# Power_Management.net
KiCad netlist of a schematic drawn in Altium Designer
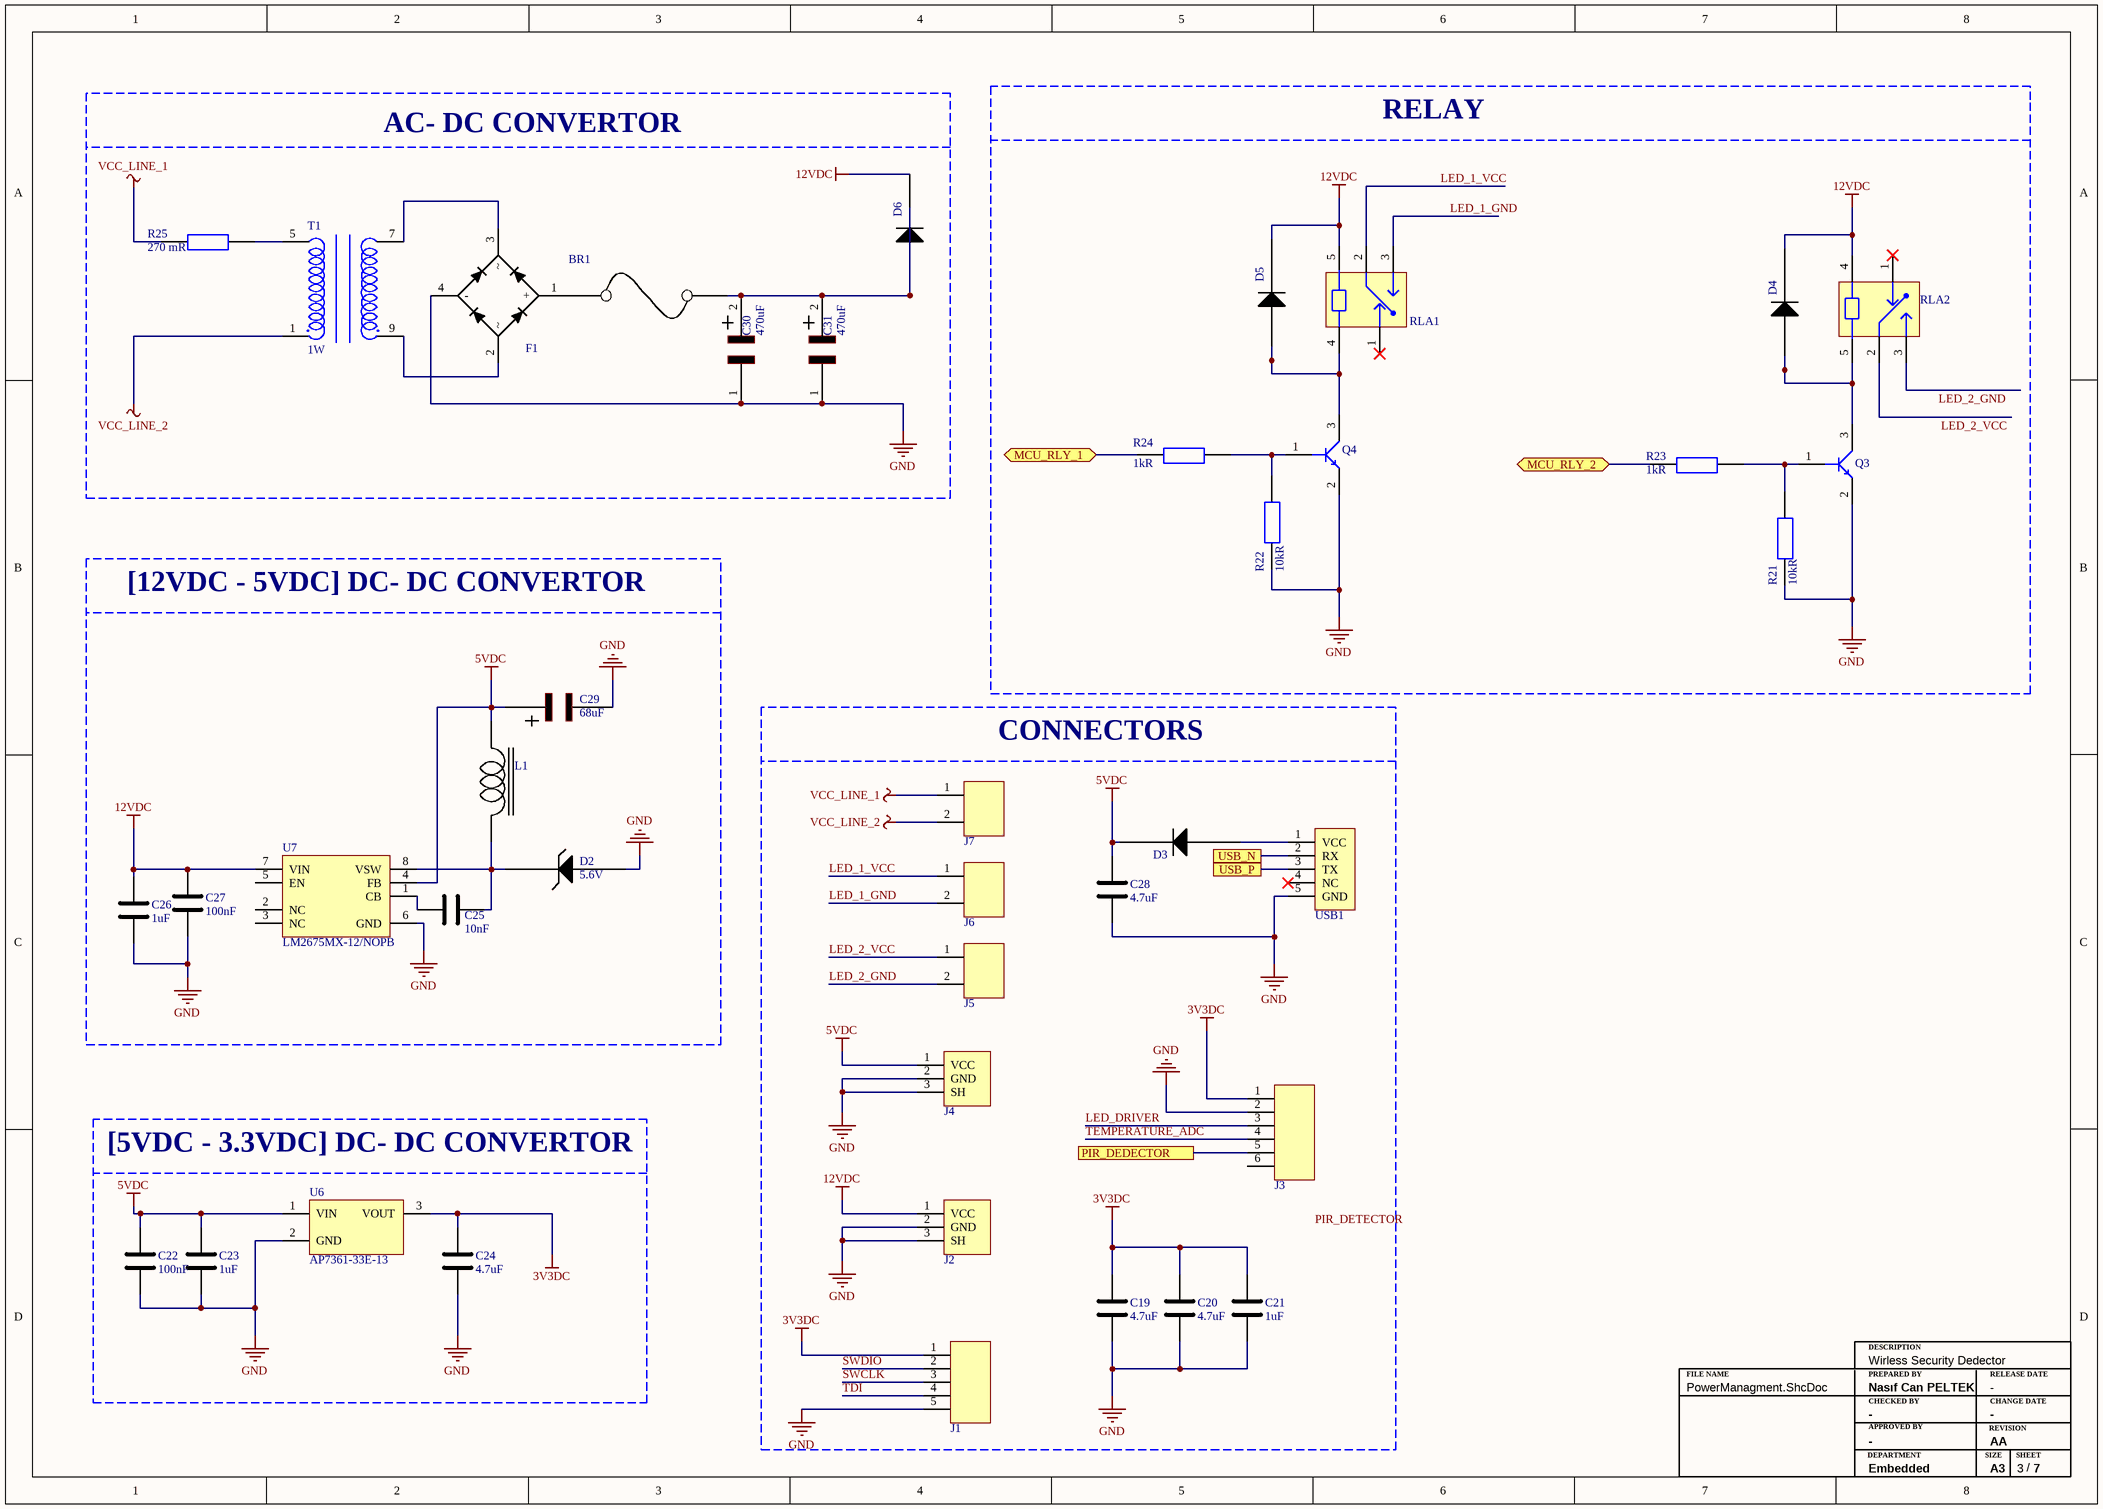
[diagram p0: Power_Management.SchDoc]

(export (version "E")
  (design (tool "Eeschema 10.0.6"))
  (components
    (comp (ref "BR1")
      (value "DB105S")
      (footprint "DB105S")
      (description "Bridge Rect 1PHASE 600V 1A Db-s")
      (fields
        (field (name "MANUFACTURER") "Sangdest Microelectronics")
        (field (name "DESIGNED BY") "Nasıf Can Peltek")
      )
      (libsource (lib "OV_00_Library") (part "DB105S"))
    )
    (comp (ref "C19")
      (value "CL21A475KAQNNNE")
      (footprint "CAP_805")
      (description "CAP CER 4.7UF 25V 10% 0805")
      (fields
        (field (name "MANUFACTURER") "Samsung")
        (field (name "TOLERANCE") "10%")
        (field (name "CAPACITANCE") "4.7uF")
        (field (name "DESIGNED BY") "Nasıf Can Peltek")
      )
      (libsource (lib "OV_00_Library") (part "CAP CER 4.7uF 0805"))
    )
    (comp (ref "C20")
      (value "CL21A475KAQNNNE")
      (footprint "CAP_805")
      (description "CAP CER 4.7UF 25V 10% 0805")
      (fields
        (field (name "MANUFACTURER") "Samsung")
        (field (name "TOLERANCE") "10%")
        (field (name "CAPACITANCE") "4.7uF")
        (field (name "DESIGNED BY") "Nasıf Can Peltek")
      )
      (libsource (lib "OV_00_Library") (part "CAP CER 4.7uF 0805"))
    )
    (comp (ref "C21")
      (value "CL21B105KBFNNNE")
      (footprint "CAP_805")
      (description "CAP CER 1UF 50V 10% 0805")
      (fields
        (field (name "MANUFACTURER") "Samsung")
        (field (name "TOLERANCE") "10%")
        (field (name "CAPACITANCE") "1uF")
        (field (name "DESIGNED BY") "Nasıf Can Peltek")
      )
      (libsource (lib "OV_00_Library") (part "CAP CER 1uF 0805"))
    )
    (comp (ref "C22")
      (value "C0603C104K5RAC7867")
      (footprint "CAP_603")
      (description "CAP CER 100nF 50V 10% SMD 0603")
      (fields
        (field (name "MANUFACTURER") "KEMET")
        (field (name "MANUFACTURER PART NUMBER") "C0603C104K5RACTU")
        (field (name "CAPACITANCE") "100nF")
        (field (name "DESIGNED BY") "Nasıf Can Peltek")
      )
      (libsource (lib "OV_00_Library") (part "CAP CER 100nF 0603"))
    )
    (comp (ref "C23")
      (value "CL21B105KBFNNNE")
      (footprint "CAP_805")
      (description "CAP CER 1UF 50V 10% 0805")
      (fields
        (field (name "MANUFACTURER") "Samsung")
        (field (name "TOLERANCE") "10%")
        (field (name "CAPACITANCE") "1uF")
        (field (name "DESIGNED BY") "Nasıf Can Peltek")
      )
      (libsource (lib "OV_00_Library") (part "CAP CER 1uF 0805"))
    )
    (comp (ref "C24")
      (value "CL21A475KAQNNNE")
      (footprint "CAP_805")
      (description "CAP CER 4.7UF 25V 10% 0805")
      (fields
        (field (name "MANUFACTURER") "Samsung")
        (field (name "TOLERANCE") "10%")
        (field (name "CAPACITANCE") "4.7uF")
        (field (name "DESIGNED BY") "Nasıf Can Peltek")
      )
      (libsource (lib "OV_00_Library") (part "CAP CER 4.7uF 0805"))
    )
    (comp (ref "C25")
      (value "0603B103K160CT")
      (footprint "CAP_603")
      (description "CAP CER 10nF 16V 10% SMD 0603")
      (fields
        (field (name "MANUFACTURER") "Walsin Technologies")
        (field (name "TOLERANCE") "10%")
        (field (name "CAPACITANCE") "10nF")
        (field (name "DESIGNED BY") "Nasıf Can Peltek")
      )
      (libsource (lib "OV_00_Library") (part "CAP CER 10nF 0603"))
    )
    (comp (ref "C26")
      (value "CL21B105KBFNNNE")
      (footprint "CAP_805")
      (description "CAP CER 1UF 50V 10% 0805")
      (fields
        (field (name "MANUFACTURER") "Samsung")
        (field (name "TOLERANCE") "10%")
        (field (name "CAPACITANCE") "1uF")
        (field (name "DESIGNED BY") "Nasıf Can Peltek")
      )
      (libsource (lib "OV_00_Library") (part "CAP CER 1uF 0805"))
    )
    (comp (ref "C27")
      (value "C0603C104K5RAC7867")
      (footprint "CAP_603")
      (description "CAP CER 100nF 50V 10% SMD 0603")
      (fields
        (field (name "MANUFACTURER") "KEMET")
        (field (name "MANUFACTURER PART NUMBER") "C0603C104K5RACTU")
        (field (name "CAPACITANCE") "100nF")
        (field (name "DESIGNED BY") "Nasıf Can Peltek")
      )
      (libsource (lib "OV_00_Library") (part "CAP CER 100nF 0603"))
    )
    (comp (ref "C28")
      (value "CL21A475KAQNNNE")
      (footprint "CAP_805")
      (description "CAP CER 4.7UF 25V 10% 0805")
      (fields
        (field (name "MANUFACTURER") "Samsung")
        (field (name "TOLERANCE") "10%")
        (field (name "CAPACITANCE") "4.7uF")
        (field (name "DESIGNED BY") "Nasıf Can Peltek")
      )
      (libsource (lib "OV_00_Library") (part "CAP CER 4.7uF 0805"))
    )
    (comp (ref "C29")
      (value "EEV686M035A9HAA")
      (footprint "CAP_EEV_Series")
      (description "Cap Aluminum Lytic 68uF 35V 20% (6.3 X 7.7mm)")
      (fields
        (field (name "MANUFACTURER") "KEMET")
        (field (name "TOLERANCE") "20%")
        (field (name "CAPACITANCE") "68uF")
        (field (name "DESIGNED BY") "Nasıf Can Peltek")
      )
      (libsource (lib "OV_00_Library") (part "CAP ALU 68uF"))
    )
    (comp (ref "C30")
      (value "ESH477M050AH4AA")
      (footprint "CAP_RADIAL_D10_P5")
      (description "Aluminum Electrolytic Capacitors Radial, Can  470 µF 50 V 2000 Hrs @ 105°C")
      (fields
        (field (name "MANUFACTURER") "KEMET")
        (field (name "TOLERANCE") "20%")
        (field (name "CAPACITANCE") "470uF")
        (field (name "DESIGNED BY") "Nasıf Can Peltek")
      )
      (libsource (lib "OV_00_Library") (part "CAP ALU 470uF"))
    )
    (comp (ref "C31")
      (value "ESH477M050AH4AA")
      (footprint "CAP_RADIAL_D10_P5")
      (description "Aluminum Electrolytic Capacitors Radial, Can  470 µF 50 V 2000 Hrs @ 105°C")
      (fields
        (field (name "MANUFACTURER") "KEMET")
        (field (name "TOLERANCE") "20%")
        (field (name "CAPACITANCE") "470uF")
        (field (name "DESIGNED BY") "Nasıf Can Peltek")
      )
      (libsource (lib "OV_00_Library") (part "CAP ALU 470uF"))
    )
    (comp (ref "D2")
      (value "1SMB5919BT3G")
      (footprint "SMB")
      (description "Zener Diode Vz=5.6V 5.32V~5.88V Izt=66.9mA")
      (fields
        (field (name "MANUFACTURER") "ON Semiconductor")
        (field (name "TOLERANCE") "5%")
        (field (name "ZENER VOLTAGE") "5.6V")
      )
      (libsource (lib "OV_00_Library") (part "1SMB5919BT3G"))
    )
    (comp (ref "D3")
      (value "1N4148WS")
      (footprint "SOD-323F")
      (description "Diode 75 V 150mA Surface Mount SOD-323F")
      (fields
        (field (name "MANUFACTURER") "ON Semiconductor / Fairchild")
        (field (name "DESIGNED BY") "Nasıf Can Peltek")
      )
      (libsource (lib "OV_00_Library") (part "1N4148WS"))
    )
    (comp (ref "D4")
      (value "1N4148WS")
      (footprint "SOD-323F")
      (description "Diode 75 V 150mA Surface Mount SOD-323F")
      (fields
        (field (name "MANUFACTURER") "ON Semiconductor / Fairchild")
        (field (name "DESIGNED BY") "Nasıf Can Peltek")
      )
      (libsource (lib "OV_00_Library") (part "1N4148WS"))
    )
    (comp (ref "D5")
      (value "1N4148WS")
      (footprint "SOD-323F")
      (description "Diode 75 V 150mA Surface Mount SOD-323F")
      (fields
        (field (name "MANUFACTURER") "ON Semiconductor / Fairchild")
        (field (name "DESIGNED BY") "Nasıf Can Peltek")
      )
      (libsource (lib "OV_00_Library") (part "1N4148WS"))
    )
    (comp (ref "D6")
      (value "1N4148WS")
      (footprint "SOD-323F")
      (description "Diode 75 V 150mA Surface Mount SOD-323F")
      (fields
        (field (name "MANUFACTURER") "ON Semiconductor / Fairchild")
        (field (name "DESIGNED BY") "Nasıf Can Peltek")
      )
      (libsource (lib "OV_00_Library") (part "1N4148WS"))
    )
    (comp (ref "F1")
      (value "FUSE_3413.0216.22")
      (footprint "FUSE_1206(3216_METRIC)")
      (description "Fuse Chip Fast Acting 1A 32V SMD Solder Pad 1206 Glass T/R VDE/cULus")
      (fields
        (field (name "MANUFACTURER") "Schurter")
        (field (name "MANUFACTURER PART NUMBER") "3413.0216.22")
      )
      (libsource (lib "OV_00_Library") (part "FUSE_3413.0216.22"))
    )
    (comp (ref "J1")
      (value "SMH-105-02-L-S")
      (footprint "PINHEADER1X5_RA")
      (description "HORIZONTAL SMT SOCKET .100 C.L.")
      (fields (field (name "MANUFACTURER") "Samtec") (field (name "DESIGNED BY") "Nasıf Can Peltek"))
      (libsource (lib "OV_00_Library") (part "SMH-105-02-L-S"))
    )
    (comp (ref "J2")
      (value "PJ-037AH-SMT-TR")
      (footprint "JACK")
      (description "Dc Power Jack Connector  2.0 x 6.3 mm, 5.0 A, Horizontal, Surface Mount (SMT),")
      (fields (field (name "MANUFACTURER") "CUI") (field (name "DESIGNED BY") "Nasıf Can Peltek"))
      (libsource (lib "OV_00_Library") (part "PJ-037AH-SMT-TR"))
    )
    (comp (ref "J3")
      (value "64800611622")
      (footprint "MALE_VERTICAL_6_PIN_CONNECTOR")
      (description "Conn, Header, 6POS, 1ROW, 1.5MM;")
      (fields
        (field (name "MANUFACTURER") "Wurth Electronics")
        (field (name "DESIGNED BY") "Nasıf Can Peltek")
      )
      (libsource (lib "OV_00_Library") (part "64800611622_6PIN_CONN"))
    )
    (comp (ref "J4")
      (value "PJ-037AH-SMT-TR")
      (footprint "JACK")
      (description "Dc Power Jack Connector  2.0 x 6.3 mm, 5.0 A, Horizontal, Surface Mount (SMT),")
      (fields (field (name "MANUFACTURER") "CUI") (field (name "DESIGNED BY") "Nasıf Can Peltek"))
      (libsource (lib "OV_00_Library") (part "PJ-037AH-SMT-TR"))
    )
    (comp (ref "J5")
      (value "TBP01R1-508-02BE")
      (footprint "TBP01R1-508")
      (description "TERMINAL BLOCK, PLUGGABLE, 5.08,")
      (fields
        (field (name "MANUFACTURER") "Laird Thermal")
        (field (name "MANUFACTURER PART NUMBER") "A10264-06")
        (field (name "DESIGNED BY") "Nasıf Can Peltek")
      )
      (libsource (lib "OV_00_Library") (part "TBP01R1-508-02BE"))
    )
    (comp (ref "J6")
      (value "TBP01R1-508-02BE")
      (footprint "TBP01R1-508")
      (description "TERMINAL BLOCK, PLUGGABLE, 5.08,")
      (fields
        (field (name "MANUFACTURER") "Laird Thermal")
        (field (name "MANUFACTURER PART NUMBER") "A10264-06")
        (field (name "DESIGNED BY") "Nasıf Can Peltek")
      )
      (libsource (lib "OV_00_Library") (part "TBP01R1-508-02BE"))
    )
    (comp (ref "J7")
      (value "TBP01R1-508-02BE")
      (footprint "TBP01R1-508")
      (description "TERMINAL BLOCK, PLUGGABLE, 5.08,")
      (fields
        (field (name "MANUFACTURER") "Laird Thermal")
        (field (name "MANUFACTURER PART NUMBER") "A10264-06")
        (field (name "DESIGNED BY") "Nasıf Can Peltek")
      )
      (libsource (lib "OV_00_Library") (part "TBP01R1-508-02BE"))
    )
    (comp (ref "L1")
      (value "78438335470")
      (footprint "IN_1212(3030 METRIC)")
      (description "Inductor (Iron Alloy Core)Fixed Ind 47UH 390MA 2.3 Ohm SMD")
      (fields
        (field (name "MANUFACTURER") "Wurth Electronics")
        (field (name "TOLERANCE") "30%")
        (field (name "DESIGNED BY") "Nasıf Can Peltek")
      )
      (libsource (lib "OV_00_Library") (part "IND 47uH"))
    )
    (comp (ref "Q3")
      (value "MMBT3904-7-F")
      (footprint "SOT_23_3")
      (description "NPN Ic=200mA Vceo=40V hfe=100~300 fT=310MHz P=300mW SOT-23")
      (fields (field (name "MANUFACTURER") "Diodes Zetex") (field (name "DESIGNED BY") "Nasıf Can Peltek"))
      (libsource (lib "OV_00_Library") (part "MMBT3904-7-F"))
    )
    (comp (ref "Q4")
      (value "MMBT3904-7-F")
      (footprint "SOT_23_3")
      (description "NPN Ic=200mA Vceo=40V hfe=100~300 fT=310MHz P=300mW SOT-23")
      (fields (field (name "MANUFACTURER") "Diodes Zetex") (field (name "DESIGNED BY") "Nasıf Can Peltek"))
      (libsource (lib "OV_00_Library") (part "MMBT3904-7-F"))
    )
    (comp (ref "R21")
      (value "RES 10K 0603")
      (footprint "RES_603")
      (description "RES SMD 10K OHM 1% 1/10W 0603 SMD")
      (fields
        (field (name "MANUFACTURER") "Yageo")
        (field (name "MANUFACTURER PART NUMBER") "RC0603FR-0710KL")
        (field (name "RESISTANCE") "10kR")
        (field (name "DESIGNED BY") "Nasıf Can Peltek")
      )
      (libsource (lib "OV_00_Library") (part "RES 10K 0603"))
    )
    (comp (ref "R22")
      (value "RES 10K 0603")
      (footprint "RES_603")
      (description "RES SMD 10K OHM 1% 1/10W 0603 SMD")
      (fields
        (field (name "MANUFACTURER") "Yageo")
        (field (name "MANUFACTURER PART NUMBER") "RC0603FR-0710KL")
        (field (name "RESISTANCE") "10kR")
        (field (name "DESIGNED BY") "Nasıf Can Peltek")
      )
      (libsource (lib "OV_00_Library") (part "RES 10K 0603"))
    )
    (comp (ref "R23")
      (value "RC0603FR-071KL")
      (footprint "RES_603")
      (description "RES SMD 1K OHM 1%  0603 SMD")
      (fields
        (field (name "MANUFACTURER") "Yageo")
        (field (name "TOLERANCE") "1%")
        (field (name "RESISTANCE") "1kR")
        (field (name "DESIGNED BY") "Nasıf Can Peltek")
      )
      (libsource (lib "OV_00_Library") (part "RES 1K 0603"))
    )
    (comp (ref "R24")
      (value "RC0603FR-071KL")
      (footprint "RES_603")
      (description "RES SMD 1K OHM 1%  0603 SMD")
      (fields
        (field (name "MANUFACTURER") "Yageo")
        (field (name "TOLERANCE") "1%")
        (field (name "RESISTANCE") "1kR")
        (field (name "DESIGNED BY") "Nasıf Can Peltek")
      )
      (libsource (lib "OV_00_Library") (part "RES 1K 0603"))
    )
    (comp (ref "R25")
      (value "5WD27")
      (footprint "RES_AXIAL_W")
      (description "Through Hole Resistor 270 mOhms ±5% 5W  Axial Wirewound")
      (fields (field (name "RESISTANCE") "270 mR") (field (name "DESIGNED BY") "Nasıf Can Peltek"))
      (libsource (lib "OV_00_Library") (part "5WD27"))
    )
    (comp (ref "RLA1")
      (value "ALQ112")
      (footprint "ALQ112")
      (description "RELAY GEN PURPOSE SPDT 10A 12V")
      (fields (field (name "MANUFACTURER") "Panasonic") (field (name "DESIGNED BY") "Nasıf Can Peltek"))
      (libsource (lib "OV_00_Library") (part "ALQ112"))
    )
    (comp (ref "RLA2")
      (value "ALQ112")
      (footprint "ALQ112")
      (description "RELAY GEN PURPOSE SPDT 10A 12V")
      (fields (field (name "MANUFACTURER") "Panasonic") (field (name "DESIGNED BY") "Nasıf Can Peltek"))
      (libsource (lib "") (part "ALQ112_1"))
    )
    (comp (ref "T1")
      (value "BV302S12010-ZU")
      (footprint "BV302S12010-ZU-X")
      (description "Power Transformers 50\\60 Hz, Laminated Transformer")
      (fields
        (field (name "MANUFACTURER") "Signal Transformer")
        (field (name "MANUFACTURER PART NUMBER") "PC-28-30")
        (field (name "MAX POWER DISSIPATION") "1W")
        (field (name "DESIGNED BY") "Nasıf Can Peltek")
      )
      (libsource (lib "OV_00_Library") (part "BV302S12010-ZU"))
    )
    (comp (ref "U6")
      (value "AP7361-33E-13")
      (footprint "SOT-223")
      (description "AP7361 Series 3.3 V 1 A Low SMT Dropout Fixed-Mode Regulator - SOT-223")
      (fields
        (field (name "MANUFACTURER") "Diodes")
        (field (name "MANUFACTURER PART NUMBER") "AP7361-33E-13")
        (field (name "DESIGNED BY") "Nasıf Can Peltek")
      )
      (libsource (lib "OV_00_Library") (part "AP7361-33E-13"))
    )
    (comp (ref "U7")
      (value "LM2675MX-12/NOPB")
      (footprint "SOIC_8")
      (fields
        (field (name "MANUFACTURER") "TI National Semiconductor")
        (field (name "MANUFACTURER PART NUMBER") "LM2675MX-12/NOPB")
        (field (name "DESIGNED BY") "Nasıf Can Peltek")
      )
      (libsource (lib "OV_00_Library") (part "LM2675MX-12/NOPB"))
    )
    (comp (ref "USB1")
      (value "10118192-0001LF")
      (footprint "MICRO_B_USB_CONNECTOR")
      (description "CONN USB MICRO B SMT R/A")
      (fields
        (field (name "MANUFACTURER") "Amphenol ICC / FCI")
        (field (name "DESIGNED BY") "Nasıf Can Peltek")
      )
      (libsource (lib "OV_00_Library") (part "Micro USB Connector"))
    )
  )
  (nets
    (net (code "1") (name "/LED_1_GND") (class "Default")
      (node (ref "J6") (pin "2") (pinfunction "2_2") (pintype "passive"))
      (node (ref "RLA1") (pin "3") (pinfunction "3_3") (pintype "passive"))
    )
    (net (code "2") (name "/LED_1_VCC") (class "Default")
      (node (ref "J6") (pin "1") (pinfunction "1_1") (pintype "passive"))
      (node (ref "RLA1") (pin "2") (pinfunction "2_2") (pintype "passive"))
    )
    (net (code "3") (name "/LED_2_GND") (class "Default")
      (node (ref "J5") (pin "2") (pinfunction "2_2") (pintype "passive"))
      (node (ref "RLA2") (pin "3") (pinfunction "3_3") (pintype "passive"))
    )
    (net (code "4") (name "/LED_2_VCC") (class "Default")
      (node (ref "J5") (pin "1") (pinfunction "1_1") (pintype "passive"))
      (node (ref "RLA2") (pin "2") (pinfunction "2_2") (pintype "passive"))
    )
    (net (code "5") (name "/LED_DRIVER") (class "Default") (node (ref "J3") (pin "3") (pintype "passive")))
    (net (code "6") (name "/MCU_RLY_1") (class "Default")
      (node (ref "R24") (pin "1") (pinfunction "1_1") (pintype "passive"))
    )
    (net (code "7") (name "/MCU_RLY_2") (class "Default")
      (node (ref "R23") (pin "1") (pinfunction "1_1") (pintype "passive"))
    )
    (net (code "8") (name "/PIR_DEDECTOR") (class "Default") (node (ref "J3") (pin "5") (pintype "passive")))
    (net (code "10") (name "/SWCLK") (class "Default")
      (node (ref "J1") (pin "3") (pinfunction "3_3") (pintype "passive"))
    )
    (net (code "11") (name "/SWDIO") (class "Default")
      (node (ref "J1") (pin "2") (pinfunction "2_2") (pintype "passive"))
    )
    (net (code "12") (name "/TDI") (class "Default")
      (node (ref "J1") (pin "4") (pinfunction "4_4") (pintype "passive"))
    )
    (net (code "13") (name "/TEMPERATURE_ADC") (class "Default")
      (node (ref "J3") (pin "4") (pintype "passive"))
    )
    (net (code "14") (name "/USB_N") (class "Default")
      (node (ref "USB1") (pin "2") (pinfunction "RX_2") (pintype "passive"))
    )
    (net (code "15") (name "/USB_P") (class "Default")
      (node (ref "USB1") (pin "3") (pinfunction "TX_3") (pintype "passive"))
    )
    (net (code "16") (name "3V3DC") (class "Default")
      (node (ref "C19") (pin "2") (pinfunction "2_2") (pintype "passive"))
      (node (ref "C20") (pin "2") (pinfunction "2_2") (pintype "passive"))
      (node (ref "C21") (pin "2") (pinfunction "2_2") (pintype "passive"))
      (node (ref "C24") (pin "2") (pinfunction "2_2") (pintype "passive"))
      (node (ref "J1") (pin "1") (pinfunction "1_1") (pintype "passive"))
      (node (ref "J3") (pin "1") (pintype "passive"))
      (node (ref "U6") (pin "3") (pinfunction "VOUT_3") (pintype "passive"))
    )
    (net (code "17") (name "5VDC") (class "Default")
      (node (ref "C22") (pin "2") (pinfunction "2_2") (pintype "passive"))
      (node (ref "C23") (pin "2") (pinfunction "2_2") (pintype "passive"))
      (node (ref "C28") (pin "2") (pinfunction "2_2") (pintype "passive"))
      (node (ref "C29") (pin "2") (pinfunction "ANODE(+)_2") (pintype "passive"))
      (node (ref "D3") (pin "2") (pinfunction "-_2") (pintype "passive"))
      (node (ref "J4") (pin "1") (pinfunction "VCC_1") (pintype "power_in"))
      (node (ref "L1") (pin "2") (pinfunction "2_2") (pintype "passive"))
      (node (ref "U6") (pin "1") (pinfunction "VIN_1") (pintype "passive"))
      (node (ref "U7") (pin "4") (pinfunction "FB_4") (pintype "passive"))
    )
    (net (code "18") (name "12VDC") (class "Default")
      (node (ref "C26") (pin "2") (pinfunction "2_2") (pintype "passive"))
      (node (ref "C27") (pin "2") (pinfunction "2_2") (pintype "passive"))
      (node (ref "D4") (pin "2") (pinfunction "-_2") (pintype "passive"))
      (node (ref "D5") (pin "2") (pinfunction "-_2") (pintype "passive"))
      (node (ref "D6") (pin "2") (pinfunction "-_2") (pintype "passive"))
      (node (ref "J2") (pin "1") (pinfunction "VCC_1") (pintype "power_in"))
      (node (ref "RLA1") (pin "5") (pinfunction "5_5") (pintype "passive"))
      (node (ref "RLA2") (pin "4") (pinfunction "4_4") (pintype "passive"))
      (node (ref "U7") (pin "7") (pinfunction "VIN_7") (pintype "passive"))
    )
    (net (code "19") (name "GND") (class "Default")
      (node (ref "BR1") (pin "4") (pinfunction "-_4") (pintype "passive"))
      (node (ref "C19") (pin "1") (pinfunction "1_1") (pintype "passive"))
      (node (ref "C20") (pin "1") (pinfunction "1_1") (pintype "passive"))
      (node (ref "C21") (pin "1") (pinfunction "1_1") (pintype "passive"))
      (node (ref "C22") (pin "1") (pinfunction "1_1") (pintype "passive"))
      (node (ref "C23") (pin "1") (pinfunction "1_1") (pintype "passive"))
      (node (ref "C24") (pin "1") (pinfunction "1_1") (pintype "passive"))
      (node (ref "C26") (pin "1") (pinfunction "1_1") (pintype "passive"))
      (node (ref "C27") (pin "1") (pinfunction "1_1") (pintype "passive"))
      (node (ref "C28") (pin "1") (pinfunction "1_1") (pintype "passive"))
      (node (ref "C29") (pin "1") (pinfunction "CATHODE(-)_1") (pintype "passive"))
      (node (ref "C30") (pin "1") (pinfunction "CATHODE(-)_1") (pintype "passive"))
      (node (ref "C31") (pin "1") (pinfunction "CATHODE(-)_1") (pintype "passive"))
      (node (ref "D2") (pin "1") (pinfunction "+_1") (pintype "passive"))
      (node (ref "J1") (pin "5") (pinfunction "5_5") (pintype "passive"))
      (node (ref "J2") (pin "2") (pinfunction "GND_2") (pintype "power_in"))
      (node (ref "J2") (pin "3") (pinfunction "SH_3") (pintype "power_in"))
      (node (ref "J3") (pin "2") (pintype "passive"))
      (node (ref "J4") (pin "2") (pinfunction "GND_2") (pintype "power_in"))
      (node (ref "J4") (pin "3") (pinfunction "SH_3") (pintype "power_in"))
      (node (ref "Q3") (pin "2") (pinfunction "E_2") (pintype "passive"))
      (node (ref "Q4") (pin "2") (pinfunction "E_2") (pintype "passive"))
      (node (ref "R21") (pin "1") (pinfunction "1_1") (pintype "passive"))
      (node (ref "R22") (pin "1") (pinfunction "1_1") (pintype "passive"))
      (node (ref "U6") (pin "2") (pinfunction "GND_2") (pintype "passive"))
      (node (ref "U7") (pin "6") (pinfunction "GND_6") (pintype "passive"))
      (node (ref "USB1") (pin "5") (pinfunction "GND_5") (pintype "passive"))
    )
    (net (code "20") (name "Net-(BR1-+)") (class "Default")
      (node (ref "BR1") (pin "1") (pinfunction "+_1") (pintype "passive"))
      (node (ref "F1") (pin "1") (pinfunction "1_1") (pintype "passive"))
    )
    (net (code "21") (name "Net-(BR1-~-Pad2)") (class "Default")
      (node (ref "BR1") (pin "2") (pinfunction "~_2") (pintype "passive"))
      (node (ref "T1") (pin "9") (pinfunction "OUTPUT_9") (pintype "passive"))
    )
    (net (code "22") (name "Net-(BR1-~-Pad3)") (class "Default")
      (node (ref "BR1") (pin "3") (pinfunction "~_3") (pintype "passive"))
      (node (ref "T1") (pin "7") (pinfunction "OUTPUT_7") (pintype "passive"))
    )
    (net (code "23") (name "Net-(C30-ANODE(+))") (class "Default")
      (node (ref "C30") (pin "2") (pinfunction "ANODE(+)_2") (pintype "passive"))
      (node (ref "C31") (pin "2") (pinfunction "ANODE(+)_2") (pintype "passive"))
      (node (ref "D6") (pin "1") (pinfunction "+_1") (pintype "passive"))
      (node (ref "F1") (pin "2") (pinfunction "2_2") (pintype "passive"))
    )
    (net (code "24") (name "Net-(D2--)") (class "Default")
      (node (ref "C25") (pin "2") (pinfunction "2_2") (pintype "passive"))
      (node (ref "D2") (pin "2") (pinfunction "-_2") (pintype "passive"))
      (node (ref "L1") (pin "1") (pinfunction "1_1") (pintype "passive"))
      (node (ref "U7") (pin "8") (pinfunction "VSW_8") (pintype "passive"))
    )
    (net (code "25") (name "Net-(D3-+)") (class "Default")
      (node (ref "D3") (pin "1") (pinfunction "+_1") (pintype "passive"))
      (node (ref "USB1") (pin "1") (pinfunction "VCC_1") (pintype "passive"))
    )
    (net (code "26") (name "Net-(D4-+)") (class "Default")
      (node (ref "D4") (pin "1") (pinfunction "+_1") (pintype "passive"))
      (node (ref "Q3") (pin "3") (pinfunction "C_3") (pintype "passive"))
      (node (ref "RLA2") (pin "5") (pinfunction "5_5") (pintype "passive"))
    )
    (net (code "27") (name "Net-(D5-+)") (class "Default")
      (node (ref "D5") (pin "1") (pinfunction "+_1") (pintype "passive"))
      (node (ref "Q4") (pin "3") (pinfunction "C_3") (pintype "passive"))
      (node (ref "RLA1") (pin "4") (pinfunction "4_4") (pintype "passive"))
    )
    (net (code "28") (name "Net-(Q3-B)") (class "Default")
      (node (ref "Q3") (pin "1") (pinfunction "B_1") (pintype "passive"))
      (node (ref "R21") (pin "2") (pinfunction "2_2") (pintype "passive"))
      (node (ref "R23") (pin "2") (pinfunction "2_2") (pintype "passive"))
    )
    (net (code "29") (name "Net-(Q4-B)") (class "Default")
      (node (ref "Q4") (pin "1") (pinfunction "B_1") (pintype "passive"))
      (node (ref "R22") (pin "2") (pinfunction "2_2") (pintype "passive"))
      (node (ref "R24") (pin "2") (pinfunction "2_2") (pintype "passive"))
    )
    (net (code "30") (name "Net-(R25-Pad2)") (class "Default")
      (node (ref "R25") (pin "2") (pinfunction "2_2") (pintype "passive"))
      (node (ref "T1") (pin "5") (pinfunction "INPUT_5") (pintype "passive"))
    )
    (net (code "31") (name "Net-(U7-CB)") (class "Default")
      (node (ref "C25") (pin "1") (pinfunction "1_1") (pintype "passive"))
      (node (ref "U7") (pin "1") (pinfunction "CB_1") (pintype "passive"))
    )
    (net (code "32") (name "VCC_LINE_1") (class "Default")
      (node (ref "J7") (pin "1") (pinfunction "1_1") (pintype "passive"))
      (node (ref "R25") (pin "1") (pinfunction "1_1") (pintype "passive"))
    )
    (net (code "33") (name "VCC_LINE_2") (class "Default")
      (node (ref "J7") (pin "2") (pinfunction "2_2") (pintype "passive"))
      (node (ref "T1") (pin "1") (pinfunction "INPUT_1") (pintype "passive"))
    )
    (net (code "34") (name "unconnected-(J3-Pad6)") (class "Default")
      (node (ref "J3") (pin "6") (pintype "passive"))
    )
    (net (code "35") (name "unconnected-(RLA1-Pad1)") (class "Default")
      (node (ref "RLA1") (pin "1") (pinfunction "1_1") (pintype "passive+no_connect"))
    )
    (net (code "36") (name "unconnected-(RLA2-Pad1)") (class "Default")
      (node (ref "RLA2") (pin "1") (pinfunction "1_1") (pintype "passive+no_connect"))
    )
    (net (code "37") (name "unconnected-(U7-EN-Pad5)") (class "Default")
      (node (ref "U7") (pin "5") (pinfunction "EN_5") (pintype "passive"))
    )
    (net (code "38") (name "unconnected-(U7-NC-Pad2)") (class "Default")
      (node (ref "U7") (pin "2") (pinfunction "NC_2") (pintype "passive"))
    )
    (net (code "39") (name "unconnected-(U7-NC-Pad3)") (class "Default")
      (node (ref "U7") (pin "3") (pinfunction "NC_3") (pintype "passive"))
    )
    (net (code "40") (name "unconnected-(USB1-NC-Pad4)") (class "Default")
      (node (ref "USB1") (pin "4") (pinfunction "NC_4") (pintype "passive+no_connect"))
    )
  )
)
